# SPF.net
KiCad netlist of a schematic drawn in EAGLE
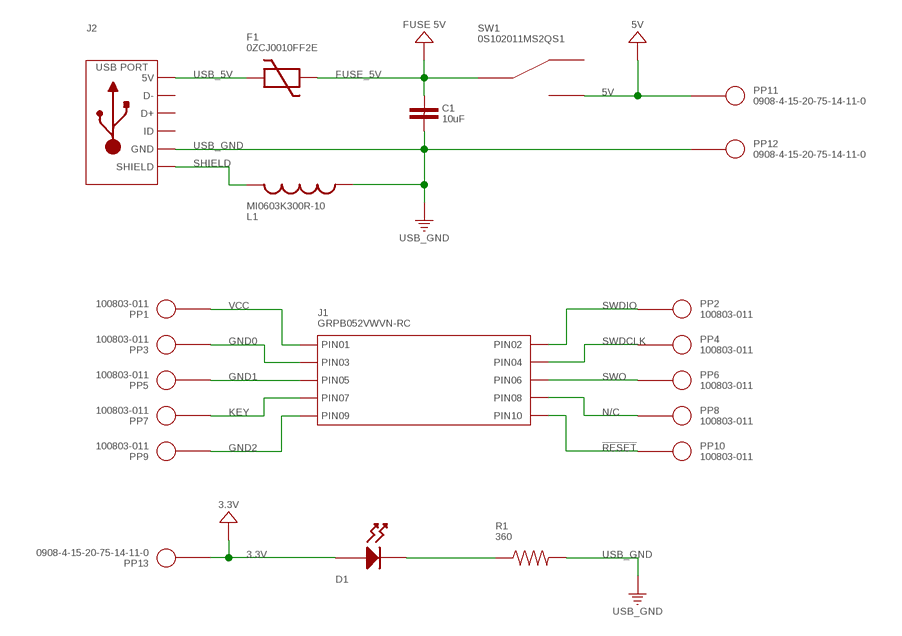
[diagram p0: schematic, sheet 1]

(export (version "E")
  (design (tool "Eeschema 10.0.6"))
  (components
    (comp (ref "C1")
      (value "10uF")
      (footprint "eagle-import:1206")
      (libsource (lib "eagle-import") (part "CAPACITOR_NON_POLAR_1206"))
    )
    (comp (ref "D1")
      (value "LED_SINGLE_0805")
      (footprint "eagle-import:LED0805")
      (libsource (lib "eagle-import") (part "LED_SINGLE_0805"))
    )
    (comp (ref "F1")
      (value "0ZCJ0010FF2E")
      (footprint "eagle-import:1206")
      (libsource (lib "eagle-import") (part "PTC_FUSE_1206"))
    )
    (comp (ref "J1")
      (value "GRPB052VWVN-RC")
      (footprint "eagle-import:GRPB052VWVN-RC")
      (fields
        (field (name "LABEL01") "VCC")
        (field (name "LABEL02") "SWDIO")
        (field (name "LABEL03") "GND")
        (field (name "LABEL04") "SWDCLK")
        (field (name "LABEL05") "GND")
        (field (name "LABEL06") "SWO")
        (field (name "LABEL09") "GND")
        (field (name "LABEL10") "!RESET")
      )
      (libsource (lib "eagle-import") (part "CON_02X05_GRPB052VWVN-RC"))
    )
    (comp (ref "J2")
      (value "USB_MICRO_RIGHT")
      (footprint "eagle-import:MICROUSB-RIGHT")
      (libsource (lib "eagle-import") (part "USB_MICRO_RIGHT"))
    )
    (comp (ref "L1")
      (value "MI0603K300R-10")
      (footprint "eagle-import:0603")
      (libsource (lib "eagle-import") (part "INDUCTOR_0603"))
    )
    (comp (ref "PP1")
      (value "100803-011")
      (footprint "eagle-import:100803_PROBE")
      (libsource (lib "eagle-import") (part "POGO_PIN_100803_PROBE"))
    )
    (comp (ref "PP2")
      (value "100803-011")
      (footprint "eagle-import:100803_PROBE")
      (libsource (lib "eagle-import") (part "POGO_PIN_100803_PROBE"))
    )
    (comp (ref "PP3")
      (value "100803-011")
      (footprint "eagle-import:100803_PROBE")
      (libsource (lib "eagle-import") (part "POGO_PIN_100803_PROBE"))
    )
    (comp (ref "PP4")
      (value "100803-011")
      (footprint "eagle-import:100803_PROBE")
      (libsource (lib "eagle-import") (part "POGO_PIN_100803_PROBE"))
    )
    (comp (ref "PP5")
      (value "100803-011")
      (footprint "eagle-import:100803_PROBE")
      (libsource (lib "eagle-import") (part "POGO_PIN_100803_PROBE"))
    )
    (comp (ref "PP6")
      (value "100803-011")
      (footprint "eagle-import:100803_PROBE")
      (libsource (lib "eagle-import") (part "POGO_PIN_100803_PROBE"))
    )
    (comp (ref "PP7")
      (value "100803-011")
      (footprint "eagle-import:100803_PROBE")
      (libsource (lib "eagle-import") (part "POGO_PIN_100803_PROBE"))
    )
    (comp (ref "PP8")
      (value "100803-011")
      (footprint "eagle-import:100803_PROBE")
      (libsource (lib "eagle-import") (part "POGO_PIN_100803_PROBE"))
    )
    (comp (ref "PP9")
      (value "100803-011")
      (footprint "eagle-import:100803_PROBE")
      (libsource (lib "eagle-import") (part "POGO_PIN_100803_PROBE"))
    )
    (comp (ref "PP10")
      (value "100803-011")
      (footprint "eagle-import:100803_PROBE")
      (libsource (lib "eagle-import") (part "POGO_PIN_100803_PROBE"))
    )
    (comp (ref "PP11")
      (value "0908-4-15-20-75-14-11-0")
      (footprint "eagle-import:0908-4-15-20-75-14-11-0")
      (libsource (lib "eagle-import") (part "POGO_PIN_0908-4-15-20-75-14-11-0"))
    )
    (comp (ref "PP12")
      (value "0908-4-15-20-75-14-11-0")
      (footprint "eagle-import:0908-4-15-20-75-14-11-0")
      (libsource (lib "eagle-import") (part "POGO_PIN_0908-4-15-20-75-14-11-0"))
    )
    (comp (ref "PP13")
      (value "0908-4-15-20-75-14-11-0")
      (footprint "eagle-import:0908-4-15-20-75-14-11-0")
      (libsource (lib "eagle-import") (part "POGO_PIN_0908-4-15-20-75-14-11-0"))
    )
    (comp (ref "R1")
      (value "360")
      (footprint "eagle-import:0805")
      (libsource (lib "eagle-import") (part "RESISTOR_0805"))
    )
    (comp (ref "SW1")
      (value "0S102011MS2QS1")
      (footprint "eagle-import:0S102011MS2QS1")
      (libsource (lib "eagle-import") (part "SPDT_0S102011MS2QS1"))
    )
  )
  (nets
    (net (code "1") (name "/GND0") (class "Default")
      (node (ref "J1") (pin "3") (pinfunction "PIN3_3") (pintype "bidirectional"))
      (node (ref "PP3") (pin "P$1") (pinfunction "P$1_P$1") (pintype "bidirectional"))
    )
    (net (code "2") (name "/GND1") (class "Default")
      (node (ref "J1") (pin "5") (pinfunction "PIN5_5") (pintype "bidirectional"))
      (node (ref "PP5") (pin "P$1") (pinfunction "P$1_P$1") (pintype "bidirectional"))
    )
    (net (code "3") (name "/GND2") (class "Default")
      (node (ref "J1") (pin "9") (pinfunction "PIN9_9") (pintype "bidirectional"))
      (node (ref "PP9") (pin "P$1") (pinfunction "P$1_P$1") (pintype "bidirectional"))
    )
    (net (code "4") (name "/KEY") (class "Default")
      (node (ref "J1") (pin "7") (pinfunction "PIN7_7") (pintype "bidirectional"))
      (node (ref "PP7") (pin "P$1") (pinfunction "P$1_P$1") (pintype "bidirectional"))
    )
    (net (code "5") (name "/N{slash}C") (class "Default")
      (node (ref "J1") (pin "8") (pinfunction "PIN8_8") (pintype "bidirectional"))
      (node (ref "PP8") (pin "P$1") (pinfunction "P$1_P$1") (pintype "bidirectional"))
    )
    (net (code "6") (name "/SHIELD") (class "Default")
      (node (ref "J2") (pin "S1") (pinfunction "SLD_S1") (pintype "power_in"))
      (node (ref "J2") (pin "S2") (pinfunction "SLD_S2") (pintype "power_in"))
      (node (ref "J2") (pin "S3") (pinfunction "SLD_S3") (pintype "power_in"))
      (node (ref "J2") (pin "S4") (pinfunction "SLD_S4") (pintype "power_in"))
      (node (ref "J2") (pin "S5") (pinfunction "SLD_S5") (pintype "power_in"))
      (node (ref "J2") (pin "S6") (pinfunction "SLD_S6") (pintype "power_in"))
      (node (ref "L1") (pin "1") (pinfunction "P$1_1") (pintype "bidirectional"))
    )
    (net (code "7") (name "/SWDCLK") (class "Default")
      (node (ref "J1") (pin "4") (pinfunction "PIN4_4") (pintype "bidirectional"))
      (node (ref "PP4") (pin "P$1") (pinfunction "P$1_P$1") (pintype "bidirectional"))
    )
    (net (code "8") (name "/SWDIO") (class "Default")
      (node (ref "J1") (pin "2") (pinfunction "PIN2_2") (pintype "bidirectional"))
      (node (ref "PP2") (pin "P$1") (pinfunction "P$1_P$1") (pintype "bidirectional"))
    )
    (net (code "9") (name "/SWO") (class "Default")
      (node (ref "J1") (pin "6") (pinfunction "PIN6_6") (pintype "bidirectional"))
      (node (ref "PP6") (pin "P$1") (pinfunction "P$1_P$1") (pintype "bidirectional"))
    )
    (net (code "10") (name "/USB_5V") (class "Default")
      (node (ref "F1") (pin "1") (pinfunction "P$1_1") (pintype "bidirectional"))
      (node (ref "J2") (pin "1") (pinfunction "5V_1") (pintype "power_in"))
    )
    (net (code "11") (name "/VCC") (class "Default")
      (node (ref "J1") (pin "1") (pinfunction "PIN1_1") (pintype "bidirectional"))
      (node (ref "PP1") (pin "P$1") (pinfunction "P$1_P$1") (pintype "bidirectional"))
    )
    (net (code "12") (name "/~{RESET}") (class "Default")
      (node (ref "J1") (pin "10") (pinfunction "PIN10_10") (pintype "bidirectional"))
      (node (ref "PP10") (pin "P$1") (pinfunction "P$1_P$1") (pintype "bidirectional"))
    )
    (net (code "13") (name "3.3V") (class "Default")
      (node (ref "D1") (pin "ANODE") (pinfunction "ANODE_ANODE") (pintype "power_in"))
      (node (ref "PP13") (pin "P$1") (pinfunction "P$1_P$1") (pintype "bidirectional"))
    )
    (net (code "14") (name "5V") (class "Default")
      (node (ref "PP11") (pin "P$1") (pinfunction "P$1_P$1") (pintype "bidirectional"))
      (node (ref "SW1") (pin "3") (pinfunction "2_3") (pintype "bidirectional"))
    )
    (net (code "15") (name "FUSE 5V") (class "Default")
      (node (ref "C1") (pin "1") (pinfunction "1_1") (pintype "passive"))
      (node (ref "F1") (pin "2") (pinfunction "P$2_2") (pintype "bidirectional"))
      (node (ref "SW1") (pin "2") (pinfunction "C_2") (pintype "bidirectional"))
    )
    (net (code "16") (name "Net-(D1-PadCATHODE)") (class "Default")
      (node (ref "D1") (pin "CATHODE") (pinfunction "CATHODE_CATHODE") (pintype "power_in"))
      (node (ref "R1") (pin "1") (pinfunction "1_1") (pintype "passive"))
    )
    (net (code "17") (name "USB_GND") (class "Default")
      (node (ref "C1") (pin "2") (pinfunction "2_2") (pintype "passive"))
      (node (ref "J2") (pin "5") (pinfunction "GND_5") (pintype "power_in"))
      (node (ref "L1") (pin "2") (pinfunction "P$2_2") (pintype "bidirectional"))
      (node (ref "PP12") (pin "P$1") (pinfunction "P$1_P$1") (pintype "bidirectional"))
      (node (ref "R1") (pin "2") (pinfunction "2_2") (pintype "passive"))
    )
    (net (code "18") (name "unconnected-(J2-D+-Pad3)") (class "Default")
      (node (ref "J2") (pin "3") (pinfunction "D+_3") (pintype "bidirectional"))
    )
    (net (code "19") (name "unconnected-(J2-D--Pad2)") (class "Default")
      (node (ref "J2") (pin "2") (pinfunction "D-_2") (pintype "bidirectional"))
    )
    (net (code "20") (name "unconnected-(J2-ID-Pad4)") (class "Default")
      (node (ref "J2") (pin "4") (pinfunction "ID_4") (pintype "bidirectional"))
    )
    (net (code "21") (name "unconnected-(SW1-Pad1)") (class "Default")
      (node (ref "SW1") (pin "1") (pinfunction "1_1") (pintype "bidirectional"))
    )
  )
)
